# driver.net
KiCad netlist of a schematic drawn in Altium Designer
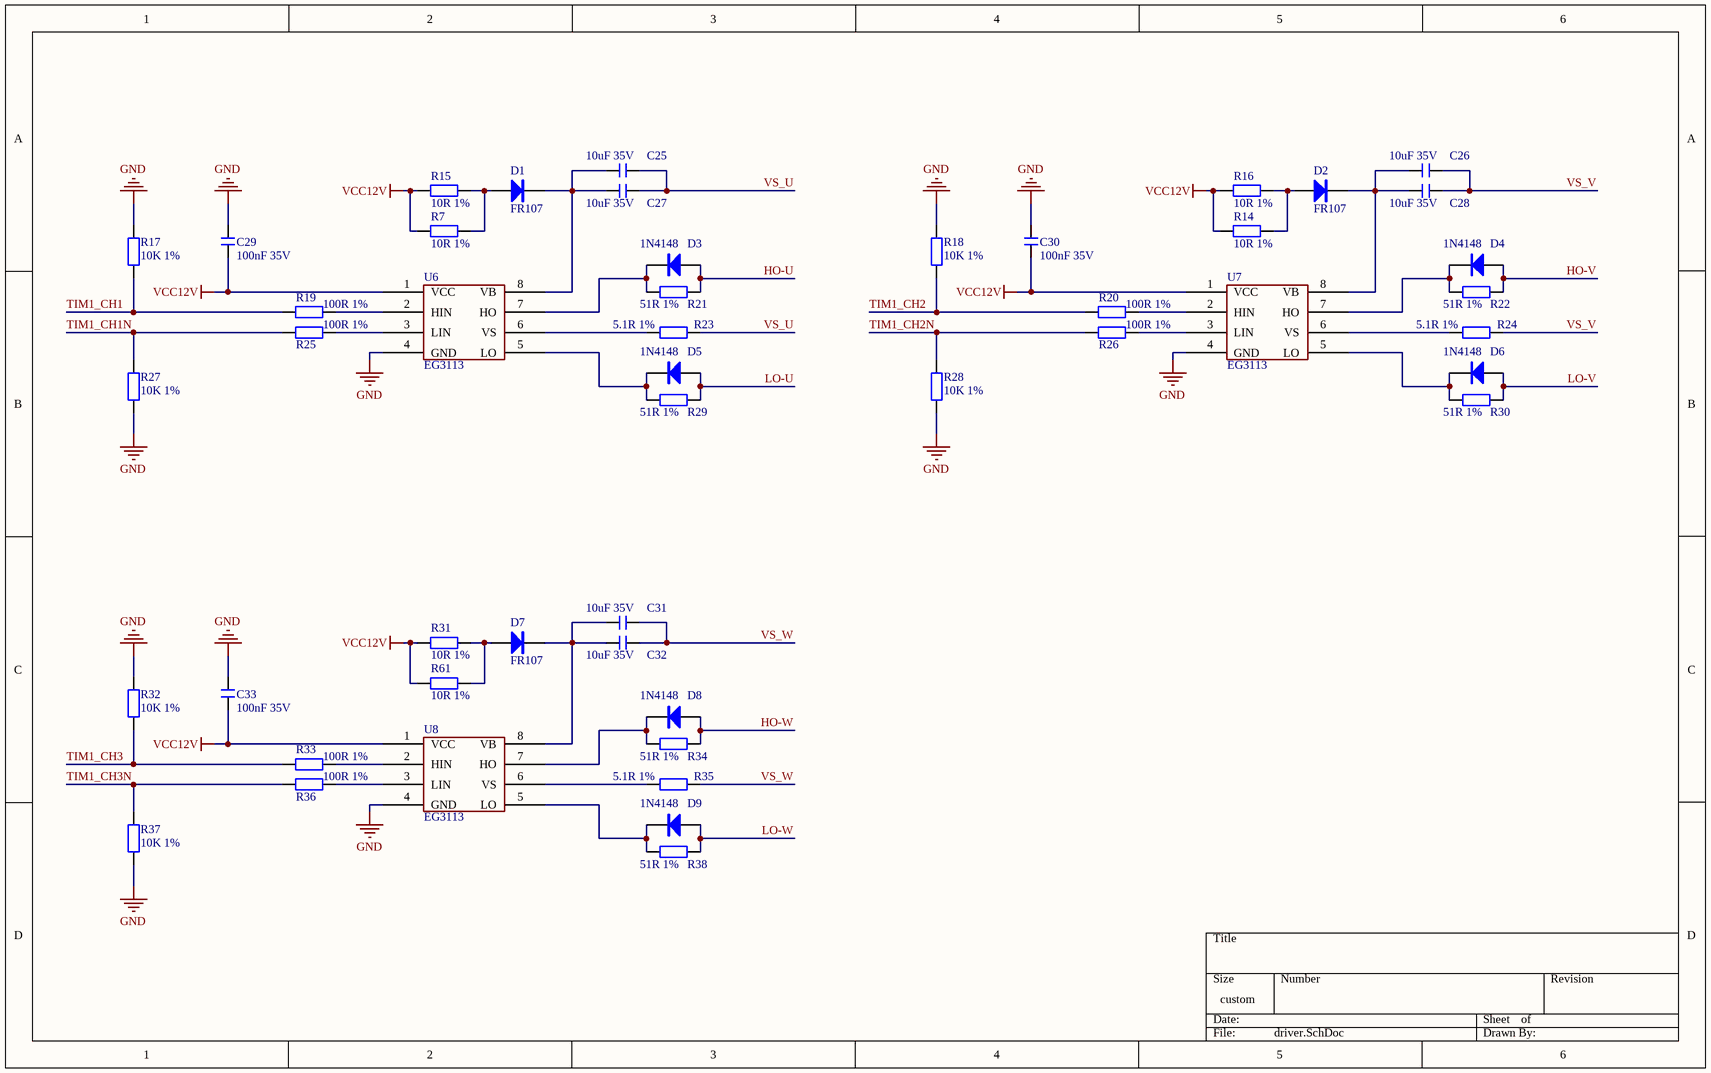
[diagram p0: driver.SchDoc]

(export (version "E")
  (design (tool "Eeschema 10.0.6"))
  (components
    (comp (ref "C25")
      (value "10uF 35V")
      (footprint "C1206_L")
      (description "无极性贴片电容")
      (fields (field (name "版权归属") "源创客"))
      (libsource (lib "Capacitor") (part "C"))
    )
    (comp (ref "C26")
      (value "10uF 35V")
      (footprint "C1206_L")
      (description "无极性贴片电容")
      (fields (field (name "版权归属") "源创客"))
      (libsource (lib "Capacitor") (part "C"))
    )
    (comp (ref "C27")
      (value "10uF 35V")
      (footprint "C1206_L")
      (description "无极性贴片电容")
      (fields (field (name "版权归属") "源创客"))
      (libsource (lib "Capacitor") (part "C"))
    )
    (comp (ref "C28")
      (value "10uF 35V")
      (footprint "C1206_L")
      (description "无极性贴片电容")
      (fields (field (name "版权归属") "源创客"))
      (libsource (lib "Capacitor") (part "C"))
    )
    (comp (ref "C29")
      (value "100nF 35V")
      (footprint "C0603_L")
      (description "无极性贴片电容")
      (fields (field (name "版权归属") "源创客"))
      (libsource (lib "Capacitor") (part "C"))
    )
    (comp (ref "C30")
      (value "100nF 35V")
      (footprint "C0603_L")
      (description "无极性贴片电容")
      (fields (field (name "版权归属") "源创客"))
      (libsource (lib "Capacitor") (part "C"))
    )
    (comp (ref "C31")
      (value "10uF 35V")
      (footprint "C1206_L")
      (description "无极性贴片电容")
      (fields (field (name "版权归属") "源创客"))
      (libsource (lib "Capacitor") (part "C"))
    )
    (comp (ref "C32")
      (value "10uF 35V")
      (footprint "C1206_L")
      (description "无极性贴片电容")
      (fields (field (name "版权归属") "源创客"))
      (libsource (lib "Capacitor") (part "C"))
    )
    (comp (ref "C33")
      (value "100nF 35V")
      (footprint "C0603_L")
      (description "无极性贴片电容")
      (fields (field (name "版权归属") "源创客"))
      (libsource (lib "Capacitor") (part "C"))
    )
    (comp (ref "D1")
      (value "FR107")
      (footprint "SOD-123")
      (description "快恢复整流二极管")
      (fields (field (name "版权归属") "源创客"))
      (libsource (lib "Diode") (part "FR107"))
    )
    (comp (ref "D2")
      (value "FR107")
      (footprint "SOD-123")
      (description "快恢复整流二极管")
      (fields (field (name "版权归属") "源创客"))
      (libsource (lib "Diode") (part "FR107"))
    )
    (comp (ref "D3")
      (value "1N4148")
      (footprint "SOD-323")
      (description "高速开关二极管")
      (fields (field (name "版权归属") "源创客"))
      (libsource (lib "Diode") (part "1N4148"))
    )
    (comp (ref "D4")
      (value "1N4148")
      (footprint "SOD-323")
      (description "高速开关二极管")
      (fields (field (name "版权归属") "源创客"))
      (libsource (lib "Diode") (part "1N4148"))
    )
    (comp (ref "D5")
      (value "1N4148")
      (footprint "SOD-323")
      (description "高速开关二极管")
      (fields (field (name "版权归属") "源创客"))
      (libsource (lib "Diode") (part "1N4148"))
    )
    (comp (ref "D6")
      (value "1N4148")
      (footprint "SOD-323")
      (description "高速开关二极管")
      (fields (field (name "版权归属") "源创客"))
      (libsource (lib "Diode") (part "1N4148"))
    )
    (comp (ref "D7")
      (value "FR107")
      (footprint "SOD-123")
      (description "快恢复整流二极管")
      (fields (field (name "版权归属") "源创客"))
      (libsource (lib "Diode") (part "FR107"))
    )
    (comp (ref "D8")
      (value "1N4148")
      (footprint "SOD-323")
      (description "高速开关二极管")
      (fields (field (name "版权归属") "源创客"))
      (libsource (lib "Diode") (part "1N4148"))
    )
    (comp (ref "D9")
      (value "1N4148")
      (footprint "SOD-323")
      (description "高速开关二极管")
      (fields (field (name "版权归属") "源创客"))
      (libsource (lib "Diode") (part "1N4148"))
    )
    (comp (ref "R7")
      (value "10R 1%")
      (footprint "R0603_l")
      (description "贴片电阻")
      (fields (field (name "版权归属") "源创客"))
      (libsource (lib "Resistor") (part "R"))
    )
    (comp (ref "R14")
      (value "10R 1%")
      (footprint "R0603_l")
      (description "贴片电阻")
      (fields (field (name "版权归属") "源创客"))
      (libsource (lib "Resistor") (part "R"))
    )
    (comp (ref "R15")
      (value "10R 1%")
      (footprint "R0603_l")
      (description "贴片电阻")
      (fields (field (name "版权归属") "源创客"))
      (libsource (lib "Resistor") (part "R"))
    )
    (comp (ref "R16")
      (value "10R 1%")
      (footprint "R0603_l")
      (description "贴片电阻")
      (fields (field (name "版权归属") "源创客"))
      (libsource (lib "Resistor") (part "R"))
    )
    (comp (ref "R17")
      (value "10K 1%")
      (footprint "R0603_l")
      (description "贴片电阻")
      (fields (field (name "版权归属") "源创客"))
      (libsource (lib "Resistor") (part "R"))
    )
    (comp (ref "R18")
      (value "10K 1%")
      (footprint "R0603_l")
      (description "贴片电阻")
      (fields (field (name "版权归属") "源创客"))
      (libsource (lib "Resistor") (part "R"))
    )
    (comp (ref "R19")
      (value "100R 1%")
      (footprint "R0603_l")
      (description "贴片电阻")
      (fields (field (name "版权归属") "源创客"))
      (libsource (lib "Resistor") (part "R"))
    )
    (comp (ref "R20")
      (value "100R 1%")
      (footprint "R0603_l")
      (description "贴片电阻")
      (fields (field (name "版权归属") "源创客"))
      (libsource (lib "Resistor") (part "R"))
    )
    (comp (ref "R21")
      (value "51R 1%")
      (footprint "R0603_l")
      (description "贴片电阻")
      (fields (field (name "版权归属") "源创客"))
      (libsource (lib "Resistor") (part "R"))
    )
    (comp (ref "R22")
      (value "51R 1%")
      (footprint "R0603_l")
      (description "贴片电阻")
      (fields (field (name "版权归属") "源创客"))
      (libsource (lib "Resistor") (part "R"))
    )
    (comp (ref "R23")
      (value "5.1R 1%")
      (footprint "R0603_l")
      (description "贴片电阻")
      (fields (field (name "版权归属") "源创客"))
      (libsource (lib "Resistor") (part "R"))
    )
    (comp (ref "R24")
      (value "5.1R 1%")
      (footprint "R0603_l")
      (description "贴片电阻")
      (fields (field (name "版权归属") "源创客"))
      (libsource (lib "Resistor") (part "R"))
    )
    (comp (ref "R25")
      (value "100R 1%")
      (footprint "R0603_l")
      (description "贴片电阻")
      (fields (field (name "版权归属") "源创客"))
      (libsource (lib "Resistor") (part "R"))
    )
    (comp (ref "R26")
      (value "100R 1%")
      (footprint "R0603_l")
      (description "贴片电阻")
      (fields (field (name "版权归属") "源创客"))
      (libsource (lib "Resistor") (part "R"))
    )
    (comp (ref "R27")
      (value "10K 1%")
      (footprint "R0603_l")
      (description "贴片电阻")
      (fields (field (name "版权归属") "源创客"))
      (libsource (lib "Resistor") (part "R"))
    )
    (comp (ref "R28")
      (value "10K 1%")
      (footprint "R0603_l")
      (description "贴片电阻")
      (fields (field (name "版权归属") "源创客"))
      (libsource (lib "Resistor") (part "R"))
    )
    (comp (ref "R29")
      (value "51R 1%")
      (footprint "R0603_l")
      (description "贴片电阻")
      (fields (field (name "版权归属") "源创客"))
      (libsource (lib "Resistor") (part "R"))
    )
    (comp (ref "R30")
      (value "51R 1%")
      (footprint "R0603_l")
      (description "贴片电阻")
      (fields (field (name "版权归属") "源创客"))
      (libsource (lib "Resistor") (part "R"))
    )
    (comp (ref "R31")
      (value "10R 1%")
      (footprint "R0603_l")
      (description "贴片电阻")
      (fields (field (name "版权归属") "源创客"))
      (libsource (lib "Resistor") (part "R"))
    )
    (comp (ref "R32")
      (value "10K 1%")
      (footprint "R0603_l")
      (description "贴片电阻")
      (fields (field (name "版权归属") "源创客"))
      (libsource (lib "Resistor") (part "R"))
    )
    (comp (ref "R33")
      (value "100R 1%")
      (footprint "R0603_l")
      (description "贴片电阻")
      (fields (field (name "版权归属") "源创客"))
      (libsource (lib "Resistor") (part "R"))
    )
    (comp (ref "R34")
      (value "51R 1%")
      (footprint "R0603_l")
      (description "贴片电阻")
      (fields (field (name "版权归属") "源创客"))
      (libsource (lib "Resistor") (part "R"))
    )
    (comp (ref "R35")
      (value "5.1R 1%")
      (footprint "R0603_l")
      (description "贴片电阻")
      (fields (field (name "版权归属") "源创客"))
      (libsource (lib "Resistor") (part "R"))
    )
    (comp (ref "R36")
      (value "100R 1%")
      (footprint "R0603_l")
      (description "贴片电阻")
      (fields (field (name "版权归属") "源创客"))
      (libsource (lib "Resistor") (part "R"))
    )
    (comp (ref "R37")
      (value "10K 1%")
      (footprint "R0603_l")
      (description "贴片电阻")
      (fields (field (name "版权归属") "源创客"))
      (libsource (lib "Resistor") (part "R"))
    )
    (comp (ref "R38")
      (value "51R 1%")
      (footprint "R0603_l")
      (description "贴片电阻")
      (fields (field (name "版权归属") "源创客"))
      (libsource (lib "Resistor") (part "R"))
    )
    (comp (ref "R61")
      (value "10R 1%")
      (footprint "R0603_l")
      (description "贴片电阻")
      (fields (field (name "版权归属") "源创客"))
      (libsource (lib "Resistor") (part "R"))
    )
    (comp (ref "U6")
      (value "EG3113")
      (footprint "SOP-8")
      (description "栅极驱动")
      (libsource (lib "栅极驱动") (part "EG3113"))
    )
    (comp (ref "U7")
      (value "EG3113")
      (footprint "SOP-8")
      (description "栅极驱动")
      (libsource (lib "栅极驱动") (part "EG3113"))
    )
    (comp (ref "U8")
      (value "EG3113")
      (footprint "SOP-8")
      (description "栅极驱动")
      (libsource (lib "栅极驱动") (part "EG3113"))
    )
  )
  (nets
    (net (code "1") (name "/HO-U") (class "Default")
      (node (ref "D3") (pin "1") (pinfunction "A_1") (pintype "passive"))
      (node (ref "R21") (pin "2") (pinfunction "2_2") (pintype "passive"))
    )
    (net (code "2") (name "/HO-V") (class "Default")
      (node (ref "D4") (pin "1") (pinfunction "A_1") (pintype "passive"))
      (node (ref "R22") (pin "2") (pinfunction "2_2") (pintype "passive"))
    )
    (net (code "3") (name "/HO-W") (class "Default")
      (node (ref "D8") (pin "1") (pinfunction "A_1") (pintype "passive"))
      (node (ref "R34") (pin "2") (pinfunction "2_2") (pintype "passive"))
    )
    (net (code "4") (name "/LO-U") (class "Default")
      (node (ref "D5") (pin "1") (pinfunction "A_1") (pintype "passive"))
      (node (ref "R29") (pin "2") (pinfunction "2_2") (pintype "passive"))
    )
    (net (code "5") (name "/LO-V") (class "Default")
      (node (ref "D6") (pin "1") (pinfunction "A_1") (pintype "passive"))
      (node (ref "R30") (pin "2") (pinfunction "2_2") (pintype "passive"))
    )
    (net (code "6") (name "/LO-W") (class "Default")
      (node (ref "D9") (pin "1") (pinfunction "A_1") (pintype "passive"))
      (node (ref "R38") (pin "2") (pinfunction "2_2") (pintype "passive"))
    )
    (net (code "7") (name "/TIM1_CH1") (class "Default")
      (node (ref "R17") (pin "1") (pinfunction "1_1") (pintype "passive"))
      (node (ref "R19") (pin "1") (pinfunction "1_1") (pintype "passive"))
    )
    (net (code "8") (name "/TIM1_CH1N") (class "Default")
      (node (ref "R25") (pin "1") (pinfunction "1_1") (pintype "passive"))
      (node (ref "R27") (pin "2") (pinfunction "2_2") (pintype "passive"))
    )
    (net (code "9") (name "/TIM1_CH2") (class "Default")
      (node (ref "R18") (pin "1") (pinfunction "1_1") (pintype "passive"))
      (node (ref "R20") (pin "1") (pinfunction "1_1") (pintype "passive"))
    )
    (net (code "10") (name "/TIM1_CH2N") (class "Default")
      (node (ref "R26") (pin "1") (pinfunction "1_1") (pintype "passive"))
      (node (ref "R28") (pin "2") (pinfunction "2_2") (pintype "passive"))
    )
    (net (code "11") (name "/TIM1_CH3") (class "Default")
      (node (ref "R32") (pin "1") (pinfunction "1_1") (pintype "passive"))
      (node (ref "R33") (pin "1") (pinfunction "1_1") (pintype "passive"))
    )
    (net (code "12") (name "/TIM1_CH3N") (class "Default")
      (node (ref "R36") (pin "1") (pinfunction "1_1") (pintype "passive"))
      (node (ref "R37") (pin "2") (pinfunction "2_2") (pintype "passive"))
    )
    (net (code "13") (name "/VS_U") (class "Default")
      (node (ref "C25") (pin "1") (pinfunction "1_1") (pintype "passive"))
      (node (ref "C27") (pin "1") (pinfunction "1_1") (pintype "passive"))
      (node (ref "R23") (pin "2") (pinfunction "2_2") (pintype "passive"))
    )
    (net (code "14") (name "/VS_V") (class "Default")
      (node (ref "C26") (pin "1") (pinfunction "1_1") (pintype "passive"))
      (node (ref "C28") (pin "1") (pinfunction "1_1") (pintype "passive"))
      (node (ref "R24") (pin "2") (pinfunction "2_2") (pintype "passive"))
    )
    (net (code "15") (name "/VS_W") (class "Default")
      (node (ref "C31") (pin "1") (pinfunction "1_1") (pintype "passive"))
      (node (ref "C32") (pin "1") (pinfunction "1_1") (pintype "passive"))
      (node (ref "R35") (pin "2") (pinfunction "2_2") (pintype "passive"))
    )
    (net (code "16") (name "GND") (class "Default")
      (node (ref "C29") (pin "1") (pinfunction "1_1") (pintype "passive"))
      (node (ref "C30") (pin "1") (pinfunction "1_1") (pintype "passive"))
      (node (ref "C33") (pin "1") (pinfunction "1_1") (pintype "passive"))
      (node (ref "R17") (pin "2") (pinfunction "2_2") (pintype "passive"))
      (node (ref "R18") (pin "2") (pinfunction "2_2") (pintype "passive"))
      (node (ref "R27") (pin "1") (pinfunction "1_1") (pintype "passive"))
      (node (ref "R28") (pin "1") (pinfunction "1_1") (pintype "passive"))
      (node (ref "R32") (pin "2") (pinfunction "2_2") (pintype "passive"))
      (node (ref "R37") (pin "1") (pinfunction "1_1") (pintype "passive"))
      (node (ref "U6") (pin "4") (pinfunction "GND_4") (pintype "passive"))
      (node (ref "U7") (pin "4") (pinfunction "GND_4") (pintype "passive"))
      (node (ref "U8") (pin "4") (pinfunction "GND_4") (pintype "passive"))
    )
    (net (code "17") (name "Net-(D1-A)") (class "Default")
      (node (ref "D1") (pin "1") (pinfunction "A_1") (pintype "passive"))
      (node (ref "R15") (pin "2") (pinfunction "2_2") (pintype "passive"))
      (node (ref "R7") (pin "2") (pinfunction "2_2") (pintype "passive"))
    )
    (net (code "18") (name "Net-(D1-K)") (class "Default")
      (node (ref "C25") (pin "2") (pinfunction "2_2") (pintype "passive"))
      (node (ref "C27") (pin "2") (pinfunction "2_2") (pintype "passive"))
      (node (ref "D1") (pin "2") (pinfunction "K_2") (pintype "passive"))
      (node (ref "U6") (pin "8") (pinfunction "VB_8") (pintype "passive"))
    )
    (net (code "19") (name "Net-(D2-A)") (class "Default")
      (node (ref "D2") (pin "1") (pinfunction "A_1") (pintype "passive"))
      (node (ref "R14") (pin "2") (pinfunction "2_2") (pintype "passive"))
      (node (ref "R16") (pin "2") (pinfunction "2_2") (pintype "passive"))
    )
    (net (code "20") (name "Net-(D2-K)") (class "Default")
      (node (ref "C26") (pin "2") (pinfunction "2_2") (pintype "passive"))
      (node (ref "C28") (pin "2") (pinfunction "2_2") (pintype "passive"))
      (node (ref "D2") (pin "2") (pinfunction "K_2") (pintype "passive"))
      (node (ref "U7") (pin "8") (pinfunction "VB_8") (pintype "passive"))
    )
    (net (code "21") (name "Net-(D3-K)") (class "Default")
      (node (ref "D3") (pin "2") (pinfunction "K_2") (pintype "passive"))
      (node (ref "R21") (pin "1") (pinfunction "1_1") (pintype "passive"))
      (node (ref "U6") (pin "7") (pinfunction "HO_7") (pintype "passive"))
    )
    (net (code "22") (name "Net-(D4-K)") (class "Default")
      (node (ref "D4") (pin "2") (pinfunction "K_2") (pintype "passive"))
      (node (ref "R22") (pin "1") (pinfunction "1_1") (pintype "passive"))
      (node (ref "U7") (pin "7") (pinfunction "HO_7") (pintype "passive"))
    )
    (net (code "23") (name "Net-(D5-K)") (class "Default")
      (node (ref "D5") (pin "2") (pinfunction "K_2") (pintype "passive"))
      (node (ref "R29") (pin "1") (pinfunction "1_1") (pintype "passive"))
      (node (ref "U6") (pin "5") (pinfunction "LO_5") (pintype "passive"))
    )
    (net (code "24") (name "Net-(D6-K)") (class "Default")
      (node (ref "D6") (pin "2") (pinfunction "K_2") (pintype "passive"))
      (node (ref "R30") (pin "1") (pinfunction "1_1") (pintype "passive"))
      (node (ref "U7") (pin "5") (pinfunction "LO_5") (pintype "passive"))
    )
    (net (code "25") (name "Net-(D7-A)") (class "Default")
      (node (ref "D7") (pin "1") (pinfunction "A_1") (pintype "passive"))
      (node (ref "R31") (pin "2") (pinfunction "2_2") (pintype "passive"))
      (node (ref "R61") (pin "2") (pinfunction "2_2") (pintype "passive"))
    )
    (net (code "26") (name "Net-(D7-K)") (class "Default")
      (node (ref "C31") (pin "2") (pinfunction "2_2") (pintype "passive"))
      (node (ref "C32") (pin "2") (pinfunction "2_2") (pintype "passive"))
      (node (ref "D7") (pin "2") (pinfunction "K_2") (pintype "passive"))
      (node (ref "U8") (pin "8") (pinfunction "VB_8") (pintype "passive"))
    )
    (net (code "27") (name "Net-(D8-K)") (class "Default")
      (node (ref "D8") (pin "2") (pinfunction "K_2") (pintype "passive"))
      (node (ref "R34") (pin "1") (pinfunction "1_1") (pintype "passive"))
      (node (ref "U8") (pin "7") (pinfunction "HO_7") (pintype "passive"))
    )
    (net (code "28") (name "Net-(D9-K)") (class "Default")
      (node (ref "D9") (pin "2") (pinfunction "K_2") (pintype "passive"))
      (node (ref "R38") (pin "1") (pinfunction "1_1") (pintype "passive"))
      (node (ref "U8") (pin "5") (pinfunction "LO_5") (pintype "passive"))
    )
    (net (code "29") (name "Net-(U6-HIN)") (class "Default")
      (node (ref "R19") (pin "2") (pinfunction "2_2") (pintype "passive"))
      (node (ref "U6") (pin "2") (pinfunction "HIN_2") (pintype "passive"))
    )
    (net (code "30") (name "Net-(U6-LIN)") (class "Default")
      (node (ref "R25") (pin "2") (pinfunction "2_2") (pintype "passive"))
      (node (ref "U6") (pin "3") (pinfunction "LIN_3") (pintype "passive"))
    )
    (net (code "31") (name "Net-(U6-VS)") (class "Default")
      (node (ref "R23") (pin "1") (pinfunction "1_1") (pintype "passive"))
      (node (ref "U6") (pin "6") (pinfunction "VS_6") (pintype "passive"))
    )
    (net (code "32") (name "Net-(U7-HIN)") (class "Default")
      (node (ref "R20") (pin "2") (pinfunction "2_2") (pintype "passive"))
      (node (ref "U7") (pin "2") (pinfunction "HIN_2") (pintype "passive"))
    )
    (net (code "33") (name "Net-(U7-LIN)") (class "Default")
      (node (ref "R26") (pin "2") (pinfunction "2_2") (pintype "passive"))
      (node (ref "U7") (pin "3") (pinfunction "LIN_3") (pintype "passive"))
    )
    (net (code "34") (name "Net-(U7-VS)") (class "Default")
      (node (ref "R24") (pin "1") (pinfunction "1_1") (pintype "passive"))
      (node (ref "U7") (pin "6") (pinfunction "VS_6") (pintype "passive"))
    )
    (net (code "35") (name "Net-(U8-HIN)") (class "Default")
      (node (ref "R33") (pin "2") (pinfunction "2_2") (pintype "passive"))
      (node (ref "U8") (pin "2") (pinfunction "HIN_2") (pintype "passive"))
    )
    (net (code "36") (name "Net-(U8-LIN)") (class "Default")
      (node (ref "R36") (pin "2") (pinfunction "2_2") (pintype "passive"))
      (node (ref "U8") (pin "3") (pinfunction "LIN_3") (pintype "passive"))
    )
    (net (code "37") (name "Net-(U8-VS)") (class "Default")
      (node (ref "R35") (pin "1") (pinfunction "1_1") (pintype "passive"))
      (node (ref "U8") (pin "6") (pinfunction "VS_6") (pintype "passive"))
    )
    (net (code "38") (name "VCC12V") (class "Default")
      (node (ref "C29") (pin "2") (pinfunction "2_2") (pintype "passive"))
      (node (ref "C30") (pin "2") (pinfunction "2_2") (pintype "passive"))
      (node (ref "C33") (pin "2") (pinfunction "2_2") (pintype "passive"))
      (node (ref "R14") (pin "1") (pinfunction "1_1") (pintype "passive"))
      (node (ref "R15") (pin "1") (pinfunction "1_1") (pintype "passive"))
      (node (ref "R16") (pin "1") (pinfunction "1_1") (pintype "passive"))
      (node (ref "R31") (pin "1") (pinfunction "1_1") (pintype "passive"))
      (node (ref "R61") (pin "1") (pinfunction "1_1") (pintype "passive"))
      (node (ref "R7") (pin "1") (pinfunction "1_1") (pintype "passive"))
      (node (ref "U6") (pin "1") (pinfunction "VCC_1") (pintype "passive"))
      (node (ref "U7") (pin "1") (pinfunction "VCC_1") (pintype "passive"))
      (node (ref "U8") (pin "1") (pinfunction "VCC_1") (pintype "passive"))
    )
  )
)
